# rascsi.net
KiCad netlist of a schematic drawn in EAGLE
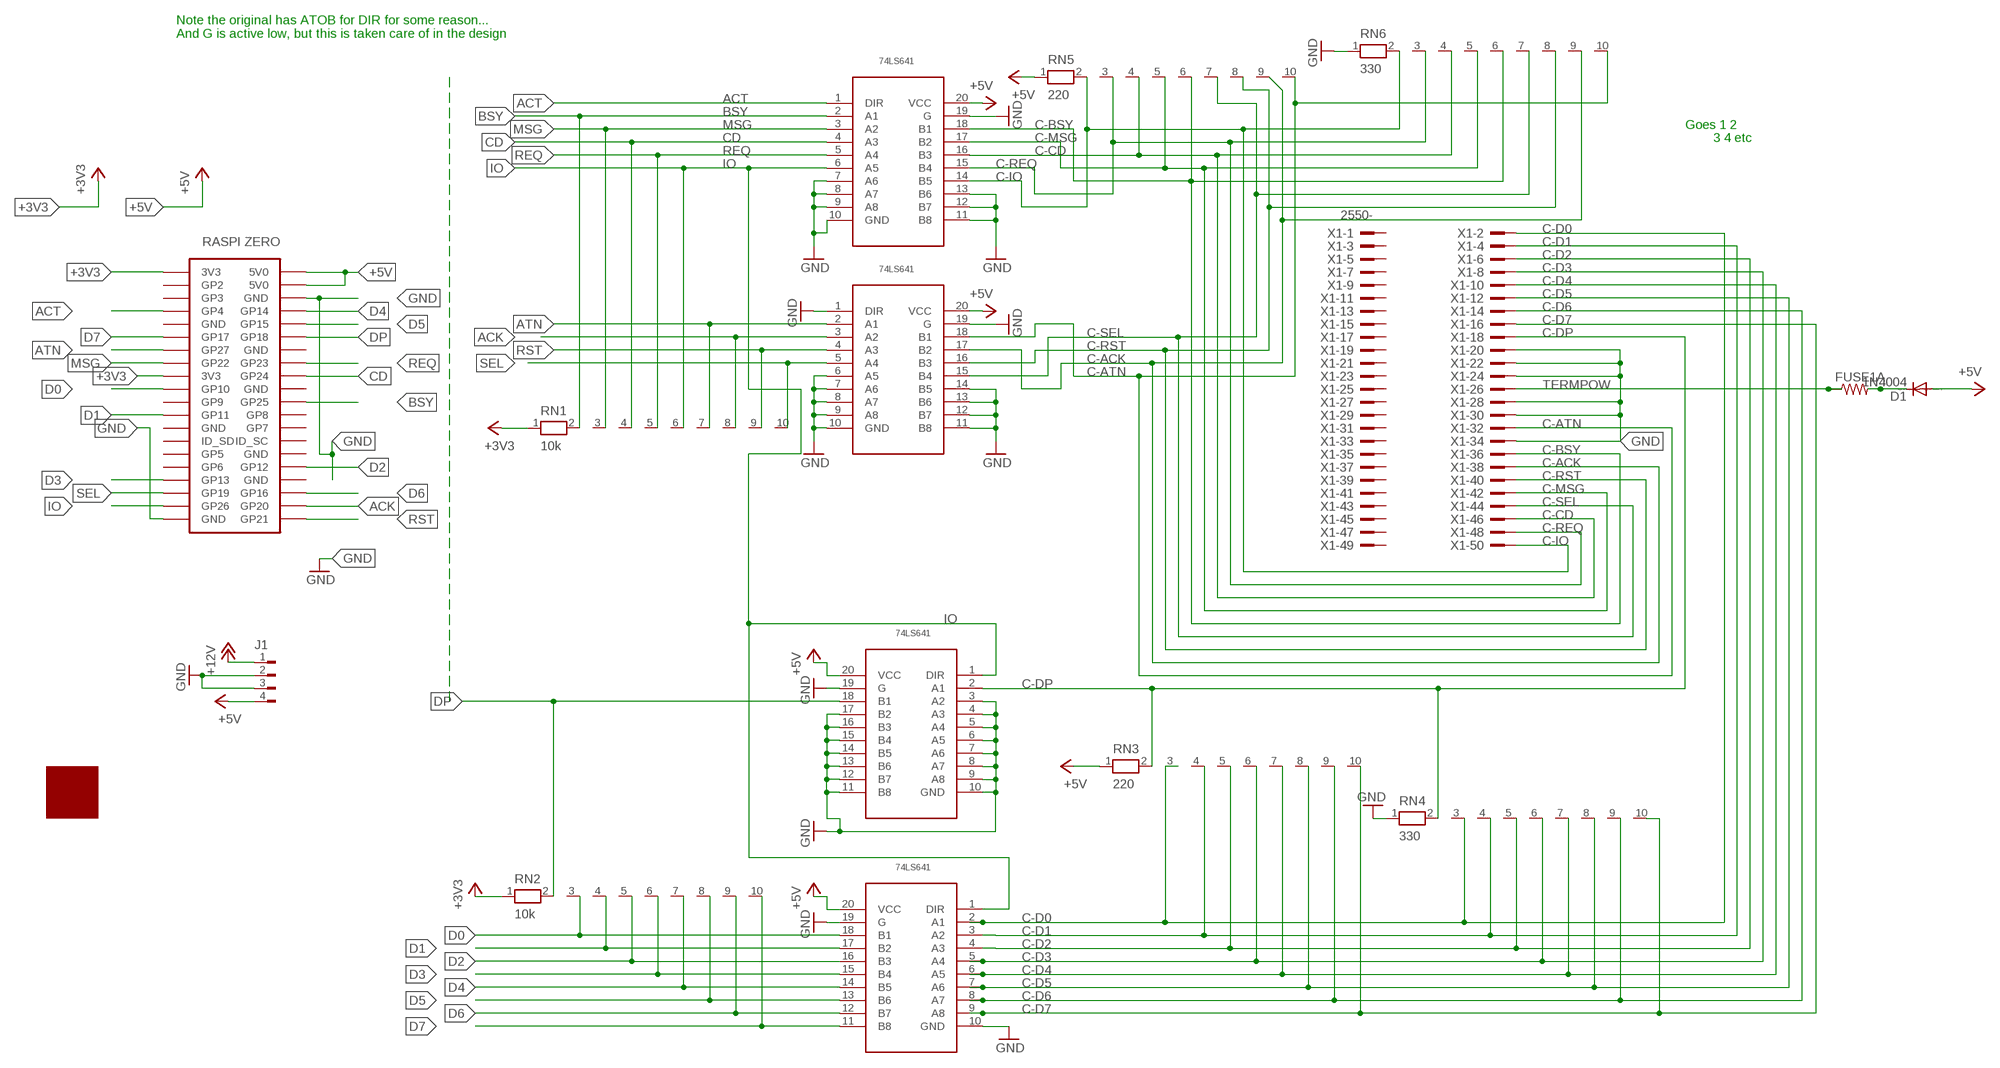
[diagram p0: schematic, sheet 1]

(export (version "E")
  (design (tool "Eeschema 10.0.6"))
  (components
    (comp (ref "D1")
      (value "1N4004")
      (footprint "eagle-import:DO41-10")
      (libsource (lib "eagle-import") (part "1N4004"))
    )
    (comp (ref "FUSE1A")
      (value "R-US_0204/7")
      (footprint "eagle-import:0204_7")
      (libsource (lib "eagle-import") (part "R-US_0204/7"))
    )
    (comp (ref "J1")
      (value "FLOP-4W")
      (footprint "eagle-import:FLOP-4V")
      (libsource (lib "eagle-import") (part "FLOP-4W"))
    )
    (comp (ref "RN1")
      (value "10k")
      (footprint "eagle-import:RN-10")
      (libsource (lib "eagle-import") (part "RN09"))
    )
    (comp (ref "RN2")
      (value "10k")
      (footprint "eagle-import:RN-10")
      (libsource (lib "eagle-import") (part "RN09"))
    )
    (comp (ref "RN3")
      (value "220")
      (footprint "eagle-import:RN-10")
      (libsource (lib "eagle-import") (part "RN09"))
    )
    (comp (ref "RN4")
      (value "330")
      (footprint "eagle-import:RN-10")
      (libsource (lib "eagle-import") (part "RN09"))
    )
    (comp (ref "RN5")
      (value "220")
      (footprint "eagle-import:RN-10")
      (libsource (lib "eagle-import") (part "RN09"))
    )
    (comp (ref "RN6")
      (value "330")
      (footprint "eagle-import:RN-10")
      (libsource (lib "eagle-import") (part "RN09"))
    )
    (comp (ref "U$1")
      (value "ZERO")
      (footprint "eagle-import:ZERO")
      (libsource (lib "eagle-import") (part "ZERO"))
    )
    (comp (ref "U$2")
      (value "LOGO")
      (footprint "eagle-import:LOGO")
      (libsource (lib "eagle-import") (part "LOGO"))
    )
    (comp (ref "U11")
      (value "SN74LS641-1SC")
      (footprint "eagle-import:SOIC20S")
      (libsource (lib "eagle-import") (part "SN74LS641-1CS"))
    )
    (comp (ref "U22")
      (value "SN74LS641-1SC")
      (footprint "eagle-import:SOIC20S")
      (libsource (lib "eagle-import") (part "SN74LS641-1CS"))
    )
    (comp (ref "U33")
      (value "SN74LS641-1SC")
      (footprint "eagle-import:SOIC20S")
      (libsource (lib "eagle-import") (part "SN74LS641-1CS"))
    )
    (comp (ref "U44")
      (value "SN74LS641-1SC")
      (footprint "eagle-import:SOIC20S")
      (libsource (lib "eagle-import") (part "SN74LS641-1CS"))
    )
    (comp (ref "X1")
      (value "2550-")
      (footprint "eagle-import:PAK100_2500-50")
      (libsource (lib "eagle-import") (part "2550-"))
    )
  )
  (nets
    (net (code "1") (name "+3V3") (class "Default")
      (node (ref "RN1") (pin "1") (pinfunction "1_1") (pintype "passive"))
      (node (ref "RN2") (pin "1") (pinfunction "1_1") (pintype "passive"))
      (node (ref "U$1") (pin "1") (pinfunction "3V3_1") (pintype "bidirectional"))
      (node (ref "U$1") (pin "17") (pinfunction "3V3_17") (pintype "bidirectional"))
    )
    (net (code "2") (name "+5V") (class "Default")
      (node (ref "D1") (pin "A") (pinfunction "A_A") (pintype "passive"))
      (node (ref "J1") (pin "4") (pinfunction "4_4") (pintype "passive"))
      (node (ref "RN3") (pin "1") (pinfunction "1_1") (pintype "passive"))
      (node (ref "RN5") (pin "1") (pinfunction "1_1") (pintype "passive"))
      (node (ref "U$1") (pin "2") (pinfunction "5V0_2") (pintype "bidirectional"))
      (node (ref "U$1") (pin "4") (pinfunction "5V0_4") (pintype "bidirectional"))
      (node (ref "U11") (pin "20") (pinfunction "VCC_20") (pintype "power_in"))
      (node (ref "U22") (pin "20") (pinfunction "VCC_20") (pintype "power_in"))
      (node (ref "U33") (pin "20") (pinfunction "VCC_20") (pintype "power_in"))
      (node (ref "U44") (pin "20") (pinfunction "VCC_20") (pintype "power_in"))
    )
    (net (code "3") (name "+12V") (class "Default")
      (node (ref "J1") (pin "1") (pinfunction "1_1") (pintype "passive"))
    )
    (net (code "4") (name "/C-ACK") (class "Default")
      (node (ref "RN5") (pin "9") (pinfunction "9_9") (pintype "passive"))
      (node (ref "RN6") (pin "9") (pinfunction "9_9") (pintype "passive"))
      (node (ref "U22") (pin "17") (pinfunction "B2_17") (pintype "bidirectional"))
      (node (ref "X1") (pin "38") (pinfunction "KL_38") (pintype "passive"))
    )
    (net (code "5") (name "/C-ATN") (class "Default")
      (node (ref "RN5") (pin "10") (pinfunction "10_10") (pintype "passive"))
      (node (ref "RN6") (pin "10") (pinfunction "10_10") (pintype "passive"))
      (node (ref "U22") (pin "18") (pinfunction "B1_18") (pintype "bidirectional"))
      (node (ref "X1") (pin "32") (pinfunction "KL_32") (pintype "passive"))
    )
    (net (code "6") (name "/C-BSY") (class "Default")
      (node (ref "RN5") (pin "6") (pinfunction "6_6") (pintype "passive"))
      (node (ref "RN6") (pin "6") (pinfunction "6_6") (pintype "passive"))
      (node (ref "U11") (pin "18") (pinfunction "B1_18") (pintype "bidirectional"))
      (node (ref "X1") (pin "36") (pinfunction "KL_36") (pintype "passive"))
    )
    (net (code "7") (name "/C-CD") (class "Default")
      (node (ref "RN5") (pin "4") (pinfunction "4_4") (pintype "passive"))
      (node (ref "RN6") (pin "4") (pinfunction "4_4") (pintype "passive"))
      (node (ref "U11") (pin "16") (pinfunction "B3_16") (pintype "bidirectional"))
      (node (ref "X1") (pin "46") (pinfunction "KL_46") (pintype "passive"))
    )
    (net (code "8") (name "/C-D0") (class "Default")
      (node (ref "RN3") (pin "3") (pinfunction "3_3") (pintype "passive"))
      (node (ref "RN4") (pin "3") (pinfunction "3_3") (pintype "passive"))
      (node (ref "U44") (pin "2") (pinfunction "A1_2") (pintype "bidirectional"))
      (node (ref "X1") (pin "2") (pinfunction "KL_2") (pintype "passive"))
    )
    (net (code "9") (name "/C-D1") (class "Default")
      (node (ref "RN3") (pin "4") (pinfunction "4_4") (pintype "passive"))
      (node (ref "RN4") (pin "4") (pinfunction "4_4") (pintype "passive"))
      (node (ref "U44") (pin "3") (pinfunction "A2_3") (pintype "bidirectional"))
      (node (ref "X1") (pin "4") (pinfunction "KL_4") (pintype "passive"))
    )
    (net (code "10") (name "/C-D2") (class "Default")
      (node (ref "RN3") (pin "5") (pinfunction "5_5") (pintype "passive"))
      (node (ref "RN4") (pin "5") (pinfunction "5_5") (pintype "passive"))
      (node (ref "U44") (pin "4") (pinfunction "A3_4") (pintype "bidirectional"))
      (node (ref "X1") (pin "6") (pinfunction "KL_6") (pintype "passive"))
    )
    (net (code "11") (name "/C-D3") (class "Default")
      (node (ref "RN3") (pin "6") (pinfunction "6_6") (pintype "passive"))
      (node (ref "RN4") (pin "6") (pinfunction "6_6") (pintype "passive"))
      (node (ref "U44") (pin "5") (pinfunction "A4_5") (pintype "bidirectional"))
      (node (ref "X1") (pin "8") (pinfunction "KL_8") (pintype "passive"))
    )
    (net (code "12") (name "/C-D4") (class "Default")
      (node (ref "RN3") (pin "7") (pinfunction "7_7") (pintype "passive"))
      (node (ref "RN4") (pin "7") (pinfunction "7_7") (pintype "passive"))
      (node (ref "U44") (pin "6") (pinfunction "A5_6") (pintype "bidirectional"))
      (node (ref "X1") (pin "10") (pinfunction "KL_10") (pintype "passive"))
    )
    (net (code "13") (name "/C-D5") (class "Default")
      (node (ref "RN3") (pin "8") (pinfunction "8_8") (pintype "passive"))
      (node (ref "RN4") (pin "8") (pinfunction "8_8") (pintype "passive"))
      (node (ref "U44") (pin "7") (pinfunction "A6_7") (pintype "bidirectional"))
      (node (ref "X1") (pin "12") (pinfunction "KL_12") (pintype "passive"))
    )
    (net (code "14") (name "/C-D6") (class "Default")
      (node (ref "RN3") (pin "9") (pinfunction "9_9") (pintype "passive"))
      (node (ref "RN4") (pin "9") (pinfunction "9_9") (pintype "passive"))
      (node (ref "U44") (pin "8") (pinfunction "A7_8") (pintype "bidirectional"))
      (node (ref "X1") (pin "14") (pinfunction "KL_14") (pintype "passive"))
    )
    (net (code "15") (name "/C-D7") (class "Default")
      (node (ref "RN3") (pin "10") (pinfunction "10_10") (pintype "passive"))
      (node (ref "RN4") (pin "10") (pinfunction "10_10") (pintype "passive"))
      (node (ref "U44") (pin "9") (pinfunction "A8_9") (pintype "bidirectional"))
      (node (ref "X1") (pin "16") (pinfunction "KL_16") (pintype "passive"))
    )
    (net (code "16") (name "/C-DP") (class "Default")
      (node (ref "RN3") (pin "2") (pinfunction "2_2") (pintype "passive"))
      (node (ref "RN4") (pin "2") (pinfunction "2_2") (pintype "passive"))
      (node (ref "U33") (pin "2") (pinfunction "A1_2") (pintype "bidirectional"))
      (node (ref "X1") (pin "18") (pinfunction "KL_18") (pintype "passive"))
    )
    (net (code "17") (name "/C-IO") (class "Default")
      (node (ref "RN5") (pin "2") (pinfunction "2_2") (pintype "passive"))
      (node (ref "RN6") (pin "2") (pinfunction "2_2") (pintype "passive"))
      (node (ref "U11") (pin "14") (pinfunction "B5_14") (pintype "bidirectional"))
      (node (ref "X1") (pin "50") (pinfunction "KL_50") (pintype "passive"))
    )
    (net (code "18") (name "/C-MSG") (class "Default")
      (node (ref "RN5") (pin "5") (pinfunction "5_5") (pintype "passive"))
      (node (ref "RN6") (pin "5") (pinfunction "5_5") (pintype "passive"))
      (node (ref "U11") (pin "17") (pinfunction "B2_17") (pintype "bidirectional"))
      (node (ref "X1") (pin "42") (pinfunction "KL_42") (pintype "passive"))
    )
    (net (code "19") (name "/C-REQ") (class "Default")
      (node (ref "RN5") (pin "3") (pinfunction "3_3") (pintype "passive"))
      (node (ref "RN6") (pin "3") (pinfunction "3_3") (pintype "passive"))
      (node (ref "U11") (pin "15") (pinfunction "B4_15") (pintype "bidirectional"))
      (node (ref "X1") (pin "48") (pinfunction "KL_48") (pintype "passive"))
    )
    (net (code "20") (name "/C-RST") (class "Default")
      (node (ref "RN5") (pin "8") (pinfunction "8_8") (pintype "passive"))
      (node (ref "RN6") (pin "8") (pinfunction "8_8") (pintype "passive"))
      (node (ref "U22") (pin "16") (pinfunction "B3_16") (pintype "bidirectional"))
      (node (ref "X1") (pin "40") (pinfunction "KL_40") (pintype "passive"))
    )
    (net (code "21") (name "/C-SEL") (class "Default")
      (node (ref "RN5") (pin "7") (pinfunction "7_7") (pintype "passive"))
      (node (ref "RN6") (pin "7") (pinfunction "7_7") (pintype "passive"))
      (node (ref "U22") (pin "15") (pinfunction "B4_15") (pintype "bidirectional"))
      (node (ref "X1") (pin "44") (pinfunction "KL_44") (pintype "passive"))
    )
    (net (code "22") (name "/TERMPOW") (class "Default")
      (node (ref "FUSE1A") (pin "1") (pinfunction "1_1") (pintype "passive"))
      (node (ref "X1") (pin "26") (pinfunction "KL_26") (pintype "passive"))
    )
    (net (code "23") (name "ACK") (class "Default")
      (node (ref "RN1") (pin "8") (pinfunction "8_8") (pintype "passive"))
      (node (ref "U$1") (pin "38") (pinfunction "GP20_38") (pintype "bidirectional"))
      (node (ref "U22") (pin "3") (pinfunction "A2_3") (pintype "bidirectional"))
    )
    (net (code "24") (name "ACT") (class "Default")
      (node (ref "U$1") (pin "7") (pinfunction "GP4_7") (pintype "bidirectional"))
      (node (ref "U11") (pin "1") (pinfunction "DIR_1") (pintype "bidirectional"))
    )
    (net (code "25") (name "ATN") (class "Default")
      (node (ref "RN1") (pin "7") (pinfunction "7_7") (pintype "passive"))
      (node (ref "U$1") (pin "13") (pinfunction "GP27_13") (pintype "bidirectional"))
      (node (ref "U22") (pin "2") (pinfunction "A1_2") (pintype "bidirectional"))
    )
    (net (code "26") (name "BSY") (class "Default")
      (node (ref "RN1") (pin "2") (pinfunction "2_2") (pintype "passive"))
      (node (ref "U$1") (pin "22") (pinfunction "GP25_22") (pintype "bidirectional"))
      (node (ref "U11") (pin "2") (pinfunction "A1_2") (pintype "bidirectional"))
    )
    (net (code "27") (name "CD") (class "Default")
      (node (ref "RN1") (pin "4") (pinfunction "4_4") (pintype "passive"))
      (node (ref "U$1") (pin "18") (pinfunction "GP24_18") (pintype "bidirectional"))
      (node (ref "U11") (pin "4") (pinfunction "A3_4") (pintype "bidirectional"))
    )
    (net (code "28") (name "D0") (class "Default")
      (node (ref "RN2") (pin "3") (pinfunction "3_3") (pintype "passive"))
      (node (ref "U$1") (pin "19") (pinfunction "GP10_19") (pintype "bidirectional"))
      (node (ref "U44") (pin "18") (pinfunction "B1_18") (pintype "bidirectional"))
    )
    (net (code "29") (name "D1") (class "Default")
      (node (ref "RN2") (pin "4") (pinfunction "4_4") (pintype "passive"))
      (node (ref "U$1") (pin "23") (pinfunction "GP11_23") (pintype "bidirectional"))
      (node (ref "U44") (pin "17") (pinfunction "B2_17") (pintype "bidirectional"))
    )
    (net (code "30") (name "D2") (class "Default")
      (node (ref "RN2") (pin "5") (pinfunction "5_5") (pintype "passive"))
      (node (ref "U$1") (pin "32") (pinfunction "GP12_32") (pintype "bidirectional"))
      (node (ref "U44") (pin "16") (pinfunction "B3_16") (pintype "bidirectional"))
    )
    (net (code "31") (name "D3") (class "Default")
      (node (ref "RN2") (pin "6") (pinfunction "6_6") (pintype "passive"))
      (node (ref "U$1") (pin "33") (pinfunction "GP13_33") (pintype "bidirectional"))
      (node (ref "U44") (pin "15") (pinfunction "B4_15") (pintype "bidirectional"))
    )
    (net (code "32") (name "D4") (class "Default")
      (node (ref "RN2") (pin "7") (pinfunction "7_7") (pintype "passive"))
      (node (ref "U$1") (pin "8") (pinfunction "GP14_8") (pintype "bidirectional"))
      (node (ref "U44") (pin "14") (pinfunction "B5_14") (pintype "bidirectional"))
    )
    (net (code "33") (name "D5") (class "Default")
      (node (ref "RN2") (pin "8") (pinfunction "8_8") (pintype "passive"))
      (node (ref "U$1") (pin "10") (pinfunction "GP15_10") (pintype "bidirectional"))
      (node (ref "U44") (pin "13") (pinfunction "B6_13") (pintype "bidirectional"))
    )
    (net (code "34") (name "D6") (class "Default")
      (node (ref "RN2") (pin "9") (pinfunction "9_9") (pintype "passive"))
      (node (ref "U$1") (pin "36") (pinfunction "GP16_36") (pintype "bidirectional"))
      (node (ref "U44") (pin "12") (pinfunction "B7_12") (pintype "bidirectional"))
    )
    (net (code "35") (name "D7") (class "Default")
      (node (ref "RN2") (pin "10") (pinfunction "10_10") (pintype "passive"))
      (node (ref "U$1") (pin "11") (pinfunction "GP17_11") (pintype "bidirectional"))
      (node (ref "U44") (pin "11") (pinfunction "B8_11") (pintype "bidirectional"))
    )
    (net (code "36") (name "DP") (class "Default")
      (node (ref "RN2") (pin "2") (pinfunction "2_2") (pintype "passive"))
      (node (ref "U$1") (pin "12") (pinfunction "GP18_12") (pintype "bidirectional"))
      (node (ref "U33") (pin "18") (pinfunction "B1_18") (pintype "bidirectional"))
    )
    (net (code "37") (name "GND") (class "Default")
      (node (ref "J1") (pin "2") (pinfunction "2_2") (pintype "passive"))
      (node (ref "J1") (pin "3") (pinfunction "3_3") (pintype "passive"))
      (node (ref "RN4") (pin "1") (pinfunction "1_1") (pintype "passive"))
      (node (ref "RN6") (pin "1") (pinfunction "1_1") (pintype "passive"))
      (node (ref "U$1") (pin "39") (pinfunction "GND_39") (pintype "bidirectional"))
      (node (ref "U$1") (pin "6") (pinfunction "GND_6") (pintype "bidirectional"))
      (node (ref "U11") (pin "10") (pinfunction "GND_10") (pintype "power_in"))
      (node (ref "U11") (pin "11") (pinfunction "B8_11") (pintype "bidirectional"))
      (node (ref "U11") (pin "12") (pinfunction "B7_12") (pintype "bidirectional"))
      (node (ref "U11") (pin "13") (pinfunction "B6_13") (pintype "bidirectional"))
      (node (ref "U11") (pin "19") (pinfunction "G_19") (pintype "bidirectional"))
      (node (ref "U11") (pin "7") (pinfunction "A6_7") (pintype "bidirectional"))
      (node (ref "U11") (pin "8") (pinfunction "A7_8") (pintype "bidirectional"))
      (node (ref "U11") (pin "9") (pinfunction "A8_9") (pintype "bidirectional"))
      (node (ref "U22") (pin "1") (pinfunction "DIR_1") (pintype "bidirectional"))
      (node (ref "U22") (pin "10") (pinfunction "GND_10") (pintype "power_in"))
      (node (ref "U22") (pin "11") (pinfunction "B8_11") (pintype "bidirectional"))
      (node (ref "U22") (pin "12") (pinfunction "B7_12") (pintype "bidirectional"))
      (node (ref "U22") (pin "13") (pinfunction "B6_13") (pintype "bidirectional"))
      (node (ref "U22") (pin "14") (pinfunction "B5_14") (pintype "bidirectional"))
      (node (ref "U22") (pin "19") (pinfunction "G_19") (pintype "bidirectional"))
      (node (ref "U22") (pin "6") (pinfunction "A5_6") (pintype "bidirectional"))
      (node (ref "U22") (pin "7") (pinfunction "A6_7") (pintype "bidirectional"))
      (node (ref "U22") (pin "8") (pinfunction "A7_8") (pintype "bidirectional"))
      (node (ref "U22") (pin "9") (pinfunction "A8_9") (pintype "bidirectional"))
      (node (ref "U33") (pin "10") (pinfunction "GND_10") (pintype "power_in"))
      (node (ref "U33") (pin "11") (pinfunction "B8_11") (pintype "bidirectional"))
      (node (ref "U33") (pin "12") (pinfunction "B7_12") (pintype "bidirectional"))
      (node (ref "U33") (pin "13") (pinfunction "B6_13") (pintype "bidirectional"))
      (node (ref "U33") (pin "14") (pinfunction "B5_14") (pintype "bidirectional"))
      (node (ref "U33") (pin "15") (pinfunction "B4_15") (pintype "bidirectional"))
      (node (ref "U33") (pin "16") (pinfunction "B3_16") (pintype "bidirectional"))
      (node (ref "U33") (pin "17") (pinfunction "B2_17") (pintype "bidirectional"))
      (node (ref "U33") (pin "19") (pinfunction "G_19") (pintype "bidirectional"))
      (node (ref "U33") (pin "3") (pinfunction "A2_3") (pintype "bidirectional"))
      (node (ref "U33") (pin "4") (pinfunction "A3_4") (pintype "bidirectional"))
      (node (ref "U33") (pin "5") (pinfunction "A4_5") (pintype "bidirectional"))
      (node (ref "U33") (pin "6") (pinfunction "A5_6") (pintype "bidirectional"))
      (node (ref "U33") (pin "7") (pinfunction "A6_7") (pintype "bidirectional"))
      (node (ref "U33") (pin "8") (pinfunction "A7_8") (pintype "bidirectional"))
      (node (ref "U33") (pin "9") (pinfunction "A8_9") (pintype "bidirectional"))
      (node (ref "U44") (pin "10") (pinfunction "GND_10") (pintype "power_in"))
      (node (ref "U44") (pin "19") (pinfunction "G_19") (pintype "bidirectional"))
      (node (ref "X1") (pin "20") (pinfunction "KL_20") (pintype "passive"))
      (node (ref "X1") (pin "22") (pinfunction "KL_22") (pintype "passive"))
      (node (ref "X1") (pin "24") (pinfunction "KL_24") (pintype "passive"))
      (node (ref "X1") (pin "28") (pinfunction "KL_28") (pintype "passive"))
      (node (ref "X1") (pin "30") (pinfunction "KL_30") (pintype "passive"))
      (node (ref "X1") (pin "34") (pinfunction "KL_34") (pintype "passive"))
    )
    (net (code "38") (name "IO") (class "Default")
      (node (ref "RN1") (pin "6") (pinfunction "6_6") (pintype "passive"))
      (node (ref "U$1") (pin "37") (pinfunction "GP26_37") (pintype "bidirectional"))
      (node (ref "U11") (pin "6") (pinfunction "A5_6") (pintype "bidirectional"))
      (node (ref "U33") (pin "1") (pinfunction "DIR_1") (pintype "bidirectional"))
      (node (ref "U44") (pin "1") (pinfunction "DIR_1") (pintype "bidirectional"))
    )
    (net (code "39") (name "MSG") (class "Default")
      (node (ref "RN1") (pin "3") (pinfunction "3_3") (pintype "passive"))
      (node (ref "U$1") (pin "15") (pinfunction "GP22_15") (pintype "bidirectional"))
      (node (ref "U11") (pin "3") (pinfunction "A2_3") (pintype "bidirectional"))
    )
    (net (code "40") (name "Net-(D1-PadC)") (class "Default")
      (node (ref "D1") (pin "C") (pinfunction "C_C") (pintype "passive"))
      (node (ref "FUSE1A") (pin "2") (pinfunction "2_2") (pintype "passive"))
    )
    (net (code "41") (name "REQ") (class "Default")
      (node (ref "RN1") (pin "5") (pinfunction "5_5") (pintype "passive"))
      (node (ref "U$1") (pin "16") (pinfunction "GP23_16") (pintype "bidirectional"))
      (node (ref "U11") (pin "5") (pinfunction "A4_5") (pintype "bidirectional"))
    )
    (net (code "42") (name "RST") (class "Default")
      (node (ref "RN1") (pin "9") (pinfunction "9_9") (pintype "passive"))
      (node (ref "U$1") (pin "40") (pinfunction "GP21_40") (pintype "bidirectional"))
      (node (ref "U22") (pin "4") (pinfunction "A3_4") (pintype "bidirectional"))
    )
    (net (code "43") (name "SEL") (class "Default")
      (node (ref "RN1") (pin "10") (pinfunction "10_10") (pintype "passive"))
      (node (ref "U$1") (pin "35") (pinfunction "GP19_35") (pintype "bidirectional"))
      (node (ref "U22") (pin "5") (pinfunction "A4_5") (pintype "bidirectional"))
    )
    (net (code "44") (name "unconnected-(U$1-GND-Pad9)") (class "Default")
      (node (ref "U$1") (pin "9") (pinfunction "GND_9") (pintype "bidirectional"))
    )
    (net (code "45") (name "unconnected-(U$1-GND-Pad14)") (class "Default")
      (node (ref "U$1") (pin "14") (pinfunction "GND_14") (pintype "bidirectional"))
    )
    (net (code "46") (name "unconnected-(U$1-GND-Pad20)") (class "Default")
      (node (ref "U$1") (pin "20") (pinfunction "GND_20") (pintype "bidirectional"))
    )
    (net (code "47") (name "unconnected-(U$1-GND-Pad25)") (class "Default")
      (node (ref "U$1") (pin "25") (pinfunction "GND_25") (pintype "bidirectional"))
    )
    (net (code "48") (name "unconnected-(U$1-GND-Pad30)") (class "Default")
      (node (ref "U$1") (pin "30") (pinfunction "GND_30") (pintype "bidirectional"))
    )
    (net (code "49") (name "unconnected-(U$1-GND-Pad34)") (class "Default")
      (node (ref "U$1") (pin "34") (pinfunction "GND_34") (pintype "bidirectional"))
    )
    (net (code "50") (name "unconnected-(U$1-GP2-Pad3)") (class "Default")
      (node (ref "U$1") (pin "3") (pinfunction "GP2_3") (pintype "bidirectional"))
    )
    (net (code "51") (name "unconnected-(U$1-GP3-Pad5)") (class "Default")
      (node (ref "U$1") (pin "5") (pinfunction "GP3_5") (pintype "bidirectional"))
    )
    (net (code "52") (name "unconnected-(U$1-GP5-Pad29)") (class "Default")
      (node (ref "U$1") (pin "29") (pinfunction "GP5_29") (pintype "bidirectional"))
    )
    (net (code "53") (name "unconnected-(U$1-GP6-Pad31)") (class "Default")
      (node (ref "U$1") (pin "31") (pinfunction "GP6_31") (pintype "bidirectional"))
    )
    (net (code "54") (name "unconnected-(U$1-GP7-Pad26)") (class "Default")
      (node (ref "U$1") (pin "26") (pinfunction "GP7_26") (pintype "bidirectional"))
    )
    (net (code "55") (name "unconnected-(U$1-GP8-Pad24)") (class "Default")
      (node (ref "U$1") (pin "24") (pinfunction "GP8_24") (pintype "bidirectional"))
    )
    (net (code "56") (name "unconnected-(U$1-GP9-Pad21)") (class "Default")
      (node (ref "U$1") (pin "21") (pinfunction "GP9_21") (pintype "bidirectional"))
    )
    (net (code "57") (name "unconnected-(U$1-ID_SC-Pad28)") (class "Default")
      (node (ref "U$1") (pin "28") (pinfunction "ID_SC_28") (pintype "bidirectional"))
    )
    (net (code "58") (name "unconnected-(U$1-ID_SD-Pad27)") (class "Default")
      (node (ref "U$1") (pin "27") (pinfunction "ID_SD_27") (pintype "bidirectional"))
    )
    (net (code "59") (name "unconnected-(X1A-KL-Pad1)") (class "Default")
      (node (ref "X1") (pin "1") (pinfunction "KL_1") (pintype "passive"))
    )
    (net (code "60") (name "unconnected-(X1AA-KL-Pad33)") (class "Default")
      (node (ref "X1") (pin "33") (pinfunction "KL_33") (pintype "passive"))
    )
    (net (code "61") (name "unconnected-(X1AC-KL-Pad35)") (class "Default")
      (node (ref "X1") (pin "35") (pinfunction "KL_35") (pintype "passive"))
    )
    (net (code "62") (name "unconnected-(X1AE-KL-Pad37)") (class "Default")
      (node (ref "X1") (pin "37") (pinfunction "KL_37") (pintype "passive"))
    )
    (net (code "63") (name "unconnected-(X1AG-KL-Pad39)") (class "Default")
      (node (ref "X1") (pin "39") (pinfunction "KL_39") (pintype "passive"))
    )
    (net (code "64") (name "unconnected-(X1AJ-KL-Pad41)") (class "Default")
      (node (ref "X1") (pin "41") (pinfunction "KL_41") (pintype "passive"))
    )
    (net (code "65") (name "unconnected-(X1AL-KL-Pad43)") (class "Default")
      (node (ref "X1") (pin "43") (pinfunction "KL_43") (pintype "passive"))
    )
    (net (code "66") (name "unconnected-(X1AN-KL-Pad45)") (class "Default")
      (node (ref "X1") (pin "45") (pinfunction "KL_45") (pintype "passive"))
    )
    (net (code "67") (name "unconnected-(X1AP-KL-Pad47)") (class "Default")
      (node (ref "X1") (pin "47") (pinfunction "KL_47") (pintype "passive"))
    )
    (net (code "68") (name "unconnected-(X1AR-KL-Pad49)") (class "Default")
      (node (ref "X1") (pin "49") (pinfunction "KL_49") (pintype "passive"))
    )
    (net (code "69") (name "unconnected-(X1AS-KL-Pad5)") (class "Default")
      (node (ref "X1") (pin "5") (pinfunction "KL_5") (pintype "passive"))
    )
    (net (code "70") (name "unconnected-(X1AV-KL-Pad7)") (class "Default")
      (node (ref "X1") (pin "7") (pinfunction "KL_7") (pintype "passive"))
    )
    (net (code "71") (name "unconnected-(X1AX-KL-Pad9)") (class "Default")
      (node (ref "X1") (pin "9") (pinfunction "KL_9") (pintype "passive"))
    )
    (net (code "72") (name "unconnected-(X1C-KL-Pad11)") (class "Default")
      (node (ref "X1") (pin "11") (pinfunction "KL_11") (pintype "passive"))
    )
    (net (code "73") (name "unconnected-(X1E-KL-Pad13)") (class "Default")
      (node (ref "X1") (pin "13") (pinfunction "KL_13") (pintype "passive"))
    )
    (net (code "74") (name "unconnected-(X1G-KL-Pad15)") (class "Default")
      (node (ref "X1") (pin "15") (pinfunction "KL_15") (pintype "passive"))
    )
    (net (code "75") (name "unconnected-(X1I-KL-Pad17)") (class "Default")
      (node (ref "X1") (pin "17") (pinfunction "KL_17") (pintype "passive"))
    )
    (net (code "76") (name "unconnected-(X1K-KL-Pad19)") (class "Default")
      (node (ref "X1") (pin "19") (pinfunction "KL_19") (pintype "passive"))
    )
    (net (code "77") (name "unconnected-(X1N-KL-Pad21)") (class "Default")
      (node (ref "X1") (pin "21") (pinfunction "KL_21") (pintype "passive"))
    )
    (net (code "78") (name "unconnected-(X1P-KL-Pad23)") (class "Default")
      (node (ref "X1") (pin "23") (pinfunction "KL_23") (pintype "passive"))
    )
    (net (code "79") (name "unconnected-(X1R-KL-Pad25)") (class "Default")
      (node (ref "X1") (pin "25") (pinfunction "KL_25") (pintype "passive"))
    )
    (net (code "80") (name "unconnected-(X1T-KL-Pad27)") (class "Default")
      (node (ref "X1") (pin "27") (pinfunction "KL_27") (pintype "passive"))
    )
    (net (code "81") (name "unconnected-(X1V-KL-Pad29)") (class "Default")
      (node (ref "X1") (pin "29") (pinfunction "KL_29") (pintype "passive"))
    )
    (net (code "82") (name "unconnected-(X1W-KL-Pad3)") (class "Default")
      (node (ref "X1") (pin "3") (pinfunction "KL_3") (pintype "passive"))
    )
    (net (code "83") (name "unconnected-(X1Y-KL-Pad31)") (class "Default")
      (node (ref "X1") (pin "31") (pinfunction "KL_31") (pintype "passive"))
    )
  )
)
